# SCH_4_Touch_Sensors.net
KiCad netlist of a schematic drawn in Altium Designer
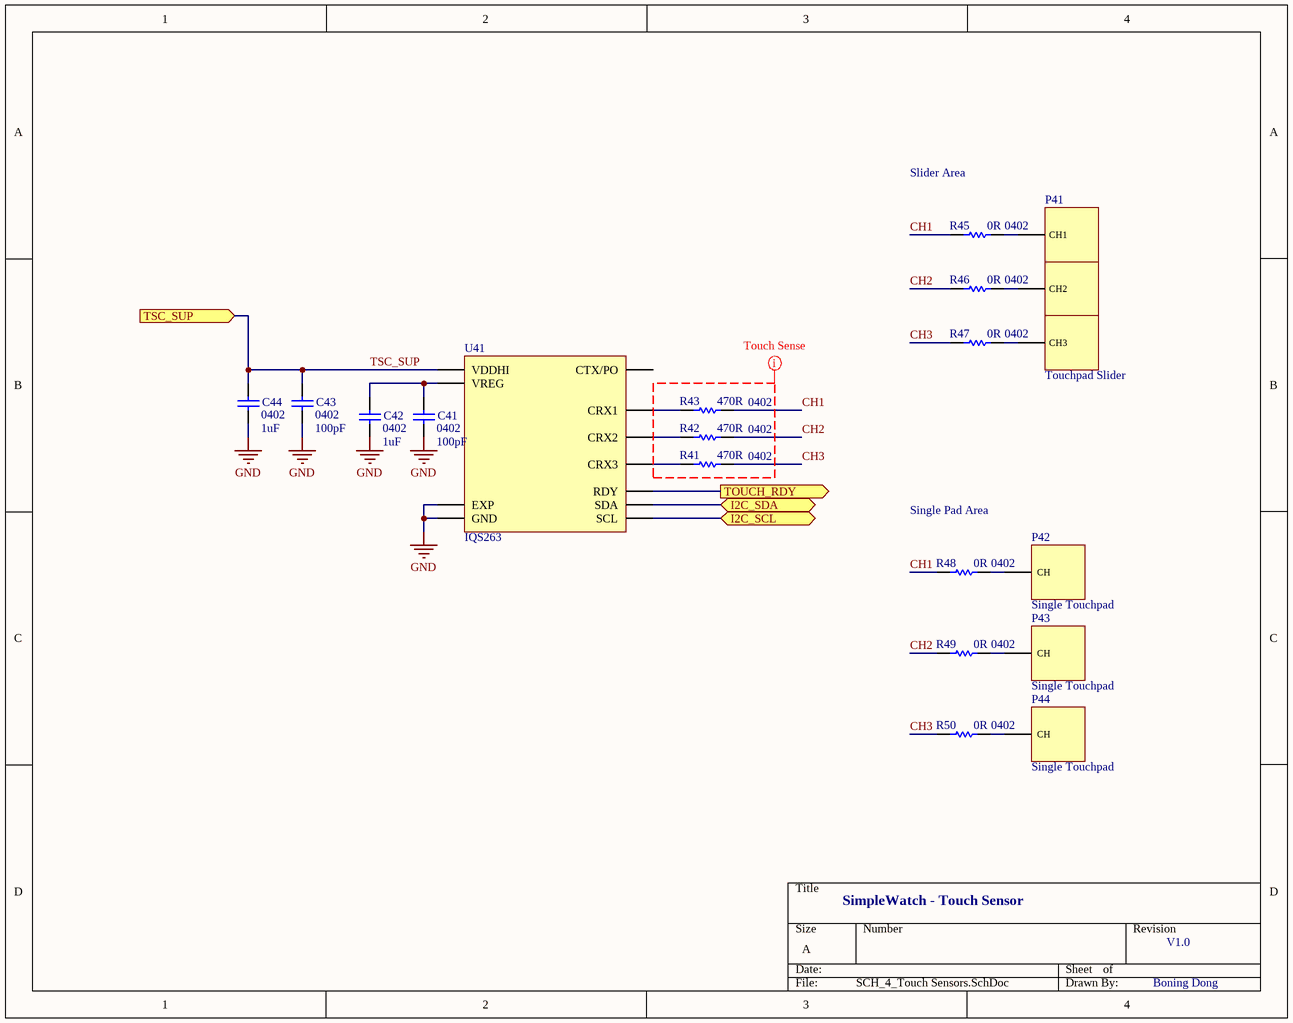
[diagram p0: SCH_4_Touch Sensors.SchDoc]

(export (version "E")
  (design (tool "Eeschema 10.0.6"))
  (components
    (comp (ref "C41")
      (value "0402")
      (footprint "CAPC1005X07N")
      (description "Capacitor")
      (fields (field (name "ALTIUM_VALUE") "100pF") (field (name "PUBLISHER") "Altium Limited"))
      (libsource (lib "Miscellaneous Devices") (part "Cap"))
    )
    (comp (ref "C42")
      (value "0402")
      (footprint "CAPC1005X07N")
      (description "Capacitor")
      (fields (field (name "ALTIUM_VALUE") "1uF") (field (name "PUBLISHER") "Altium Limited"))
      (libsource (lib "Miscellaneous Devices") (part "Cap"))
    )
    (comp (ref "C43")
      (value "0402")
      (footprint "CAPC1005X07N")
      (description "Capacitor")
      (fields (field (name "ALTIUM_VALUE") "100pF") (field (name "PUBLISHER") "Altium Limited"))
      (libsource (lib "Miscellaneous Devices") (part "Cap"))
    )
    (comp (ref "C44")
      (value "0402")
      (footprint "CAPC1005X07N")
      (description "Capacitor")
      (fields (field (name "ALTIUM_VALUE") "1uF") (field (name "PUBLISHER") "Altium Limited"))
      (libsource (lib "Miscellaneous Devices") (part "Cap"))
    )
    (comp (ref "P41")
      (value "Touchpad Slider")
      (footprint "TPAD_SLIDER_21X7")
      (description "General Slider Touchpad")
      (libsource (lib "Schematic_Touchpads") (part "PAD_SLIDER_3CH"))
    )
    (comp (ref "P42")
      (value "Single Touchpad")
      (footprint "TPAD_8X8")
      (description "General Single Touchpad")
      (libsource (lib "Schematic_Touchpads") (part "PAD_SINGLE"))
    )
    (comp (ref "P43")
      (value "Single Touchpad")
      (footprint "TPAD_8X8")
      (description "General Single Touchpad")
      (libsource (lib "Schematic_Touchpads") (part "PAD_SINGLE"))
    )
    (comp (ref "P44")
      (value "Single Touchpad")
      (footprint "TPAD_8X8")
      (description "General Single Touchpad")
      (libsource (lib "Schematic_Touchpads") (part "PAD_SINGLE"))
    )
    (comp (ref "R41")
      (value "0402")
      (footprint "RESC1005X04N")
      (description "Resistor")
      (fields (field (name "ALTIUM_VALUE") "470R") (field (name "PUBLISHER") "Altium Limited"))
      (libsource (lib "Miscellaneous Devices") (part "Res1"))
    )
    (comp (ref "R42")
      (value "0402")
      (footprint "RESC1005X04N")
      (description "Resistor")
      (fields (field (name "ALTIUM_VALUE") "470R") (field (name "PUBLISHER") "Altium Limited"))
      (libsource (lib "Miscellaneous Devices") (part "Res1"))
    )
    (comp (ref "R43")
      (value "0402")
      (footprint "RESC1005X04N")
      (description "Resistor")
      (fields (field (name "ALTIUM_VALUE") "470R") (field (name "PUBLISHER") "Altium Limited"))
      (libsource (lib "Miscellaneous Devices") (part "Res1"))
    )
    (comp (ref "R45")
      (value "0402")
      (footprint "RESC1005X04N")
      (description "Resistor")
      (fields (field (name "ALTIUM_VALUE") "0R") (field (name "PUBLISHER") "Altium Limited"))
      (libsource (lib "Miscellaneous Devices") (part "Res1"))
    )
    (comp (ref "R46")
      (value "0402")
      (footprint "RESC1005X04N")
      (description "Resistor")
      (fields (field (name "ALTIUM_VALUE") "0R") (field (name "PUBLISHER") "Altium Limited"))
      (libsource (lib "Miscellaneous Devices") (part "Res1"))
    )
    (comp (ref "R47")
      (value "0402")
      (footprint "RESC1005X04N")
      (description "Resistor")
      (fields (field (name "ALTIUM_VALUE") "0R") (field (name "PUBLISHER") "Altium Limited"))
      (libsource (lib "Miscellaneous Devices") (part "Res1"))
    )
    (comp (ref "R48")
      (value "0402")
      (footprint "RESC1005X04N")
      (description "Resistor")
      (fields (field (name "ALTIUM_VALUE") "0R") (field (name "PUBLISHER") "Altium Limited"))
      (libsource (lib "Miscellaneous Devices") (part "Res1"))
    )
    (comp (ref "R49")
      (value "0402")
      (footprint "RESC1005X04N")
      (description "Resistor")
      (fields (field (name "ALTIUM_VALUE") "0R") (field (name "PUBLISHER") "Altium Limited"))
      (libsource (lib "Miscellaneous Devices") (part "Res1"))
    )
    (comp (ref "R50")
      (value "0402")
      (footprint "RESC1005X04N")
      (description "Resistor")
      (fields (field (name "ALTIUM_VALUE") "0R") (field (name "PUBLISHER") "Altium Limited"))
      (libsource (lib "Miscellaneous Devices") (part "Res1"))
    )
    (comp (ref "U41")
      (value "IQS263")
      (footprint "DFN50P300X300-10N_HS240X150")
      (description "3 Channel Capacitive Touch Sensor. Capacitive Touch Buttons, Slider, Wheel 10-DFN (3x3)")
      (libsource (lib "Schematic_IC_Sensors") (part "AZOTEQ_IQS263"))
    )
  )
  (nets
    (net (code "1") (name "/CH1") (class "Default")
      (node (ref "R43") (pin "2") (pinfunction "2_2") (pintype "passive"))
      (node (ref "R45") (pin "1") (pinfunction "1_1") (pintype "passive"))
      (node (ref "R48") (pin "1") (pinfunction "1_1") (pintype "passive"))
    )
    (net (code "2") (name "/CH2") (class "Default")
      (node (ref "R42") (pin "2") (pinfunction "2_2") (pintype "passive"))
      (node (ref "R46") (pin "1") (pinfunction "1_1") (pintype "passive"))
      (node (ref "R49") (pin "1") (pinfunction "1_1") (pintype "passive"))
    )
    (net (code "3") (name "/CH3") (class "Default")
      (node (ref "R41") (pin "2") (pinfunction "2_2") (pintype "passive"))
      (node (ref "R47") (pin "1") (pinfunction "1_1") (pintype "passive"))
      (node (ref "R50") (pin "1") (pinfunction "1_1") (pintype "passive"))
    )
    (net (code "4") (name "/I2C_SCL") (class "Default")
      (node (ref "U41") (pin "8") (pinfunction "SCL_8") (pintype "passive"))
    )
    (net (code "5") (name "/I2C_SDA") (class "Default")
      (node (ref "U41") (pin "7") (pinfunction "SDA_7") (pintype "passive"))
    )
    (net (code "6") (name "/TOUCH_RDY") (class "Default")
      (node (ref "U41") (pin "6") (pinfunction "RDY_6") (pintype "passive"))
    )
    (net (code "7") (name "/TSC_SUP") (class "Default")
      (node (ref "C43") (pin "2") (pinfunction "2_2") (pintype "passive"))
      (node (ref "C44") (pin "2") (pinfunction "2_2") (pintype "passive"))
      (node (ref "U41") (pin "4") (pinfunction "VDDHI_4") (pintype "passive"))
    )
    (net (code "8") (name "GND") (class "Default")
      (node (ref "C41") (pin "1") (pinfunction "1_1") (pintype "passive"))
      (node (ref "C42") (pin "1") (pinfunction "1_1") (pintype "passive"))
      (node (ref "C43") (pin "1") (pinfunction "1_1") (pintype "passive"))
      (node (ref "C44") (pin "1") (pinfunction "1_1") (pintype "passive"))
      (node (ref "U41") (pin "1") (pinfunction "GND_1") (pintype "passive"))
      (node (ref "U41") (pin "11") (pinfunction "EXP_11") (pintype "passive"))
    )
    (net (code "9") (name "Net-(P41-CH1)") (class "Default")
      (node (ref "P41") (pin "1") (pinfunction "CH1_1") (pintype "passive"))
      (node (ref "R45") (pin "2") (pinfunction "2_2") (pintype "passive"))
    )
    (net (code "10") (name "Net-(P41-CH2)") (class "Default")
      (node (ref "P41") (pin "2") (pinfunction "CH2_2") (pintype "passive"))
      (node (ref "R46") (pin "2") (pinfunction "2_2") (pintype "passive"))
    )
    (net (code "11") (name "Net-(P41-CH3)") (class "Default")
      (node (ref "P41") (pin "3") (pinfunction "CH3_3") (pintype "passive"))
      (node (ref "R47") (pin "2") (pinfunction "2_2") (pintype "passive"))
    )
    (net (code "12") (name "Net-(P42-CH)") (class "Default")
      (node (ref "P42") (pin "1") (pinfunction "CH_1") (pintype "passive"))
      (node (ref "R48") (pin "2") (pinfunction "2_2") (pintype "passive"))
    )
    (net (code "13") (name "Net-(P43-CH)") (class "Default")
      (node (ref "P43") (pin "1") (pinfunction "CH_1") (pintype "passive"))
      (node (ref "R49") (pin "2") (pinfunction "2_2") (pintype "passive"))
    )
    (net (code "14") (name "Net-(P44-CH)") (class "Default")
      (node (ref "P44") (pin "1") (pinfunction "CH_1") (pintype "passive"))
      (node (ref "R50") (pin "2") (pinfunction "2_2") (pintype "passive"))
    )
    (net (code "15") (name "Net-(U41-CRX1)") (class "Default")
      (node (ref "R43") (pin "1") (pinfunction "1_1") (pintype "passive"))
      (node (ref "U41") (pin "2") (pinfunction "CRX1_2") (pintype "passive"))
    )
    (net (code "16") (name "Net-(U41-CRX2)") (class "Default")
      (node (ref "R42") (pin "1") (pinfunction "1_1") (pintype "passive"))
      (node (ref "U41") (pin "3") (pinfunction "CRX2_3") (pintype "passive"))
    )
    (net (code "17") (name "Net-(U41-CRX3)") (class "Default")
      (node (ref "R41") (pin "1") (pinfunction "1_1") (pintype "passive"))
      (node (ref "U41") (pin "9") (pinfunction "CRX3_9") (pintype "passive"))
    )
    (net (code "18") (name "Net-(U41-VREG)") (class "Default")
      (node (ref "C41") (pin "2") (pinfunction "2_2") (pintype "passive"))
      (node (ref "C42") (pin "2") (pinfunction "2_2") (pintype "passive"))
      (node (ref "U41") (pin "5") (pinfunction "VREG_5") (pintype "passive"))
    )
    (net (code "19") (name "unconnected-(U41-CTX{slash}PO-Pad10)") (class "Default")
      (node (ref "U41") (pin "10") (pinfunction "CTX/PO_10") (pintype "passive"))
    )
  )
)
